# umodular_shiled_amm.net
KiCad netlist of a schematic drawn in EAGLE
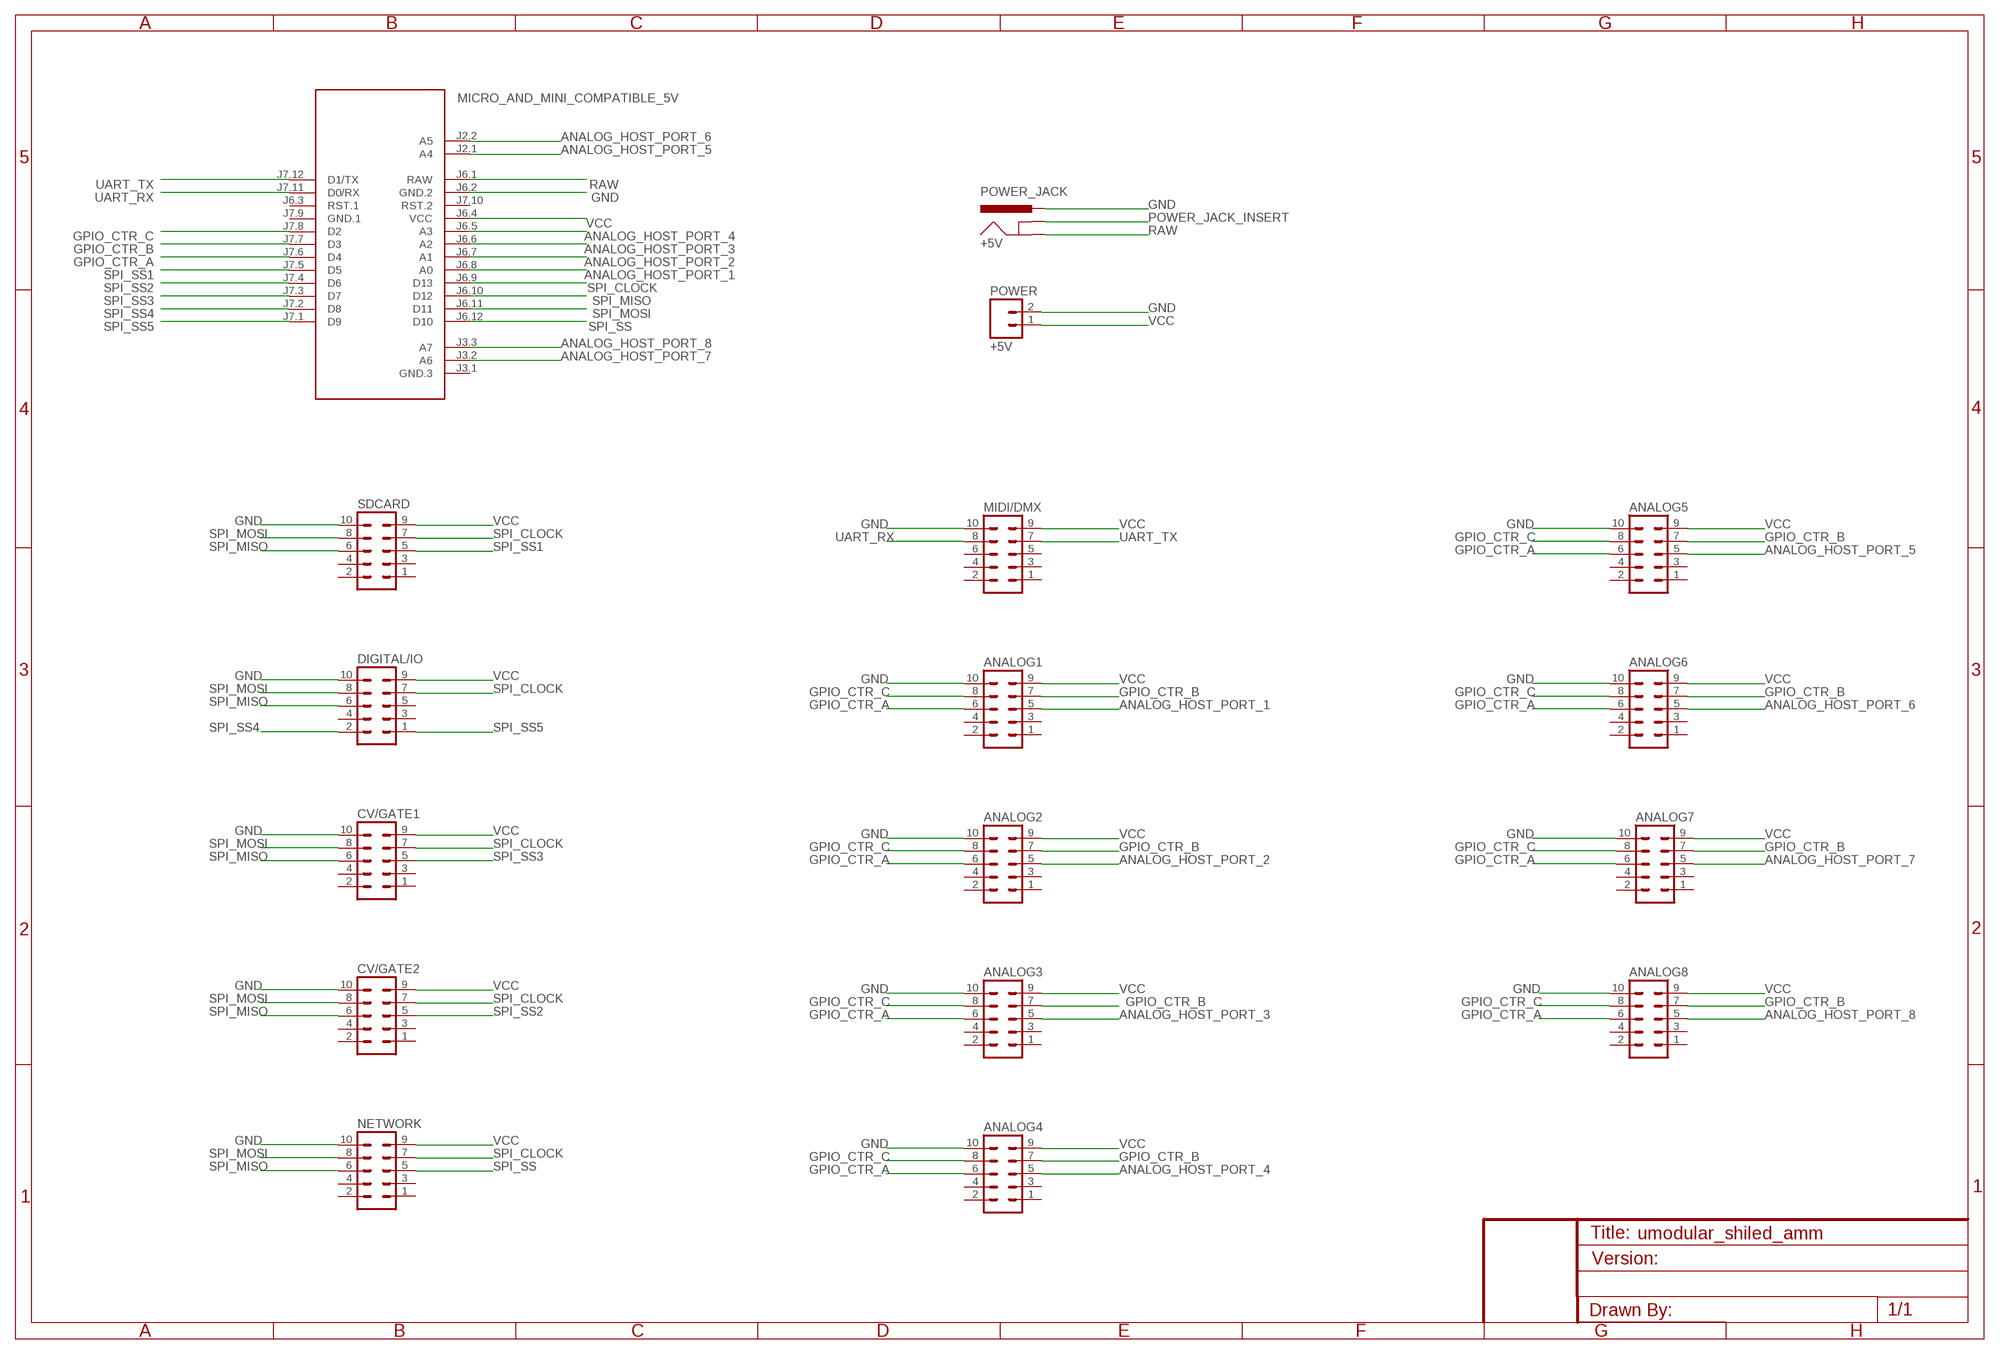
[diagram p0: schematic, sheet 1]

(export (version "E")
  (design (tool "Eeschema 10.0.6"))
  (components
    (comp (ref "+5V")
      (value "POWER_JACK")
      (footprint "eagle-import:POWER_JACK_PTH")
      (libsource (lib "eagle-import") (part "POWER_JACKPTH"))
    )
    (comp (ref "ANALOG1")
      (value "MA05-2")
      (footprint "eagle-import:MA05-2")
      (libsource (lib "eagle-import") (part "MA05-2"))
    )
    (comp (ref "ANALOG2")
      (value "MA05-2")
      (footprint "eagle-import:MA05-2")
      (libsource (lib "eagle-import") (part "MA05-2"))
    )
    (comp (ref "ANALOG3")
      (value "MA05-2")
      (footprint "eagle-import:MA05-2")
      (libsource (lib "eagle-import") (part "MA05-2"))
    )
    (comp (ref "ANALOG4")
      (value "MA05-2")
      (footprint "eagle-import:MA05-2")
      (libsource (lib "eagle-import") (part "MA05-2"))
    )
    (comp (ref "ANALOG5")
      (value "MA05-2")
      (footprint "eagle-import:MA05-2")
      (libsource (lib "eagle-import") (part "MA05-2"))
    )
    (comp (ref "ANALOG6")
      (value "MA05-2")
      (footprint "eagle-import:MA05-2")
      (libsource (lib "eagle-import") (part "MA05-2"))
    )
    (comp (ref "ANALOG7")
      (value "MA05-2")
      (footprint "eagle-import:MA05-2")
      (libsource (lib "eagle-import") (part "MA05-2"))
    )
    (comp (ref "ANALOG8")
      (value "MA05-2")
      (footprint "eagle-import:MA05-2")
      (libsource (lib "eagle-import") (part "MA05-2"))
    )
    (comp (ref "CV/GATE1")
      (value "MA05-2")
      (footprint "eagle-import:MA05-2")
      (libsource (lib "eagle-import") (part "MA05-2"))
    )
    (comp (ref "CV/GATE2")
      (value "MA05-2")
      (footprint "eagle-import:MA05-2")
      (libsource (lib "eagle-import") (part "MA05-2"))
    )
    (comp (ref "DIGITAL/IO")
      (value "MA05-2")
      (footprint "eagle-import:MA05-2")
      (libsource (lib "eagle-import") (part "MA05-2"))
    )
    (comp (ref "MICRO_AND_MINI_COMPATIBLE_5V")
      (value "ARDUINO-PRO-MINI-3.3V#NP")
      (footprint "eagle-import:ARDUINO-PRO-MINI#NP")
      (libsource (lib "eagle-import") (part "ARDUINO-PRO-MINI-#NP3.3V"))
    )
    (comp (ref "MIDI/DMX")
      (value "MA05-2")
      (footprint "eagle-import:MA05-2")
      (libsource (lib "eagle-import") (part "MA05-2"))
    )
    (comp (ref "NETWORK")
      (value "MA05-2")
      (footprint "eagle-import:MA05-2")
      (libsource (lib "eagle-import") (part "MA05-2"))
    )
    (comp (ref "POWER")
      (value "+5V")
      (footprint "eagle-import:1X02_LOCK_LONGPADS")
      (libsource (lib "eagle-import") (part "M02LOCK_LONGPADS"))
    )
    (comp (ref "SDCARD")
      (value "MA05-2")
      (footprint "eagle-import:MA05-2")
      (libsource (lib "eagle-import") (part "MA05-2"))
    )
  )
  (nets
    (net (code "1") (name "/ANALOG_HOST_PORT_1") (class "Default")
      (node (ref "ANALOG1") (pin "5") (pinfunction "5_5") (pintype "passive"))
      (node (ref "MICRO_AND_MINI_COMPATIBLE_5V") (pin "J6.8") (pinfunction "A0_J6.8") (pintype "bidirectional"))
    )
    (net (code "2") (name "/ANALOG_HOST_PORT_2") (class "Default")
      (node (ref "ANALOG2") (pin "5") (pinfunction "5_5") (pintype "passive"))
      (node (ref "MICRO_AND_MINI_COMPATIBLE_5V") (pin "J6.7") (pinfunction "A1_J6.7") (pintype "bidirectional"))
    )
    (net (code "3") (name "/ANALOG_HOST_PORT_3") (class "Default")
      (node (ref "ANALOG3") (pin "5") (pinfunction "5_5") (pintype "passive"))
      (node (ref "MICRO_AND_MINI_COMPATIBLE_5V") (pin "J6.6") (pinfunction "A2_J6.6") (pintype "bidirectional"))
    )
    (net (code "4") (name "/ANALOG_HOST_PORT_4") (class "Default")
      (node (ref "ANALOG4") (pin "5") (pinfunction "5_5") (pintype "passive"))
      (node (ref "MICRO_AND_MINI_COMPATIBLE_5V") (pin "J6.5") (pinfunction "A3_J6.5") (pintype "bidirectional"))
    )
    (net (code "5") (name "/ANALOG_HOST_PORT_5") (class "Default")
      (node (ref "ANALOG5") (pin "5") (pinfunction "5_5") (pintype "passive"))
      (node (ref "MICRO_AND_MINI_COMPATIBLE_5V") (pin "J2.1") (pinfunction "A4_J2.1") (pintype "bidirectional"))
    )
    (net (code "6") (name "/ANALOG_HOST_PORT_6") (class "Default")
      (node (ref "ANALOG6") (pin "5") (pinfunction "5_5") (pintype "passive"))
      (node (ref "MICRO_AND_MINI_COMPATIBLE_5V") (pin "J2.2") (pinfunction "A5_J2.2") (pintype "bidirectional"))
    )
    (net (code "7") (name "/ANALOG_HOST_PORT_7") (class "Default")
      (node (ref "ANALOG7") (pin "5") (pinfunction "5_5") (pintype "passive"))
      (node (ref "MICRO_AND_MINI_COMPATIBLE_5V") (pin "J3.2") (pinfunction "A6_J3.2") (pintype "bidirectional"))
    )
    (net (code "8") (name "/ANALOG_HOST_PORT_8") (class "Default")
      (node (ref "ANALOG8") (pin "5") (pinfunction "5_5") (pintype "passive"))
      (node (ref "MICRO_AND_MINI_COMPATIBLE_5V") (pin "J3.3") (pinfunction "A7_J3.3") (pintype "bidirectional"))
    )
    (net (code "9") (name "/GND") (class "Default")
      (node (ref "+5V") (pin "PWR") (pinfunction "PWR_PWR") (pintype "bidirectional"))
      (node (ref "ANALOG1") (pin "10") (pinfunction "10_10") (pintype "passive"))
      (node (ref "ANALOG2") (pin "10") (pinfunction "10_10") (pintype "passive"))
      (node (ref "ANALOG3") (pin "10") (pinfunction "10_10") (pintype "passive"))
      (node (ref "ANALOG4") (pin "10") (pinfunction "10_10") (pintype "passive"))
      (node (ref "ANALOG5") (pin "10") (pinfunction "10_10") (pintype "passive"))
      (node (ref "ANALOG6") (pin "10") (pinfunction "10_10") (pintype "passive"))
      (node (ref "ANALOG7") (pin "10") (pinfunction "10_10") (pintype "passive"))
      (node (ref "ANALOG8") (pin "10") (pinfunction "10_10") (pintype "passive"))
      (node (ref "CV/GATE1") (pin "10") (pinfunction "10_10") (pintype "passive"))
      (node (ref "CV/GATE2") (pin "10") (pinfunction "10_10") (pintype "passive"))
      (node (ref "DIGITAL/IO") (pin "10") (pinfunction "10_10") (pintype "passive"))
      (node (ref "MICRO_AND_MINI_COMPATIBLE_5V") (pin "J6.2") (pinfunction "GND.2_J6.2") (pintype "power_in"))
      (node (ref "MIDI/DMX") (pin "10") (pinfunction "10_10") (pintype "passive"))
      (node (ref "NETWORK") (pin "10") (pinfunction "10_10") (pintype "passive"))
      (node (ref "POWER") (pin "2") (pinfunction "2_2") (pintype "passive"))
      (node (ref "SDCARD") (pin "10") (pinfunction "10_10") (pintype "passive"))
    )
    (net (code "10") (name "/GND.1") (class "Default")
      (node (ref "MICRO_AND_MINI_COMPATIBLE_5V") (pin "J7.9") (pinfunction "GND.1_J7.9") (pintype "power_in"))
    )
    (net (code "11") (name "/GPIO_CTR_A") (class "Default")
      (node (ref "ANALOG1") (pin "6") (pinfunction "6_6") (pintype "passive"))
      (node (ref "ANALOG2") (pin "6") (pinfunction "6_6") (pintype "passive"))
      (node (ref "ANALOG3") (pin "6") (pinfunction "6_6") (pintype "passive"))
      (node (ref "ANALOG4") (pin "6") (pinfunction "6_6") (pintype "passive"))
      (node (ref "ANALOG5") (pin "6") (pinfunction "6_6") (pintype "passive"))
      (node (ref "ANALOG6") (pin "6") (pinfunction "6_6") (pintype "passive"))
      (node (ref "ANALOG7") (pin "6") (pinfunction "6_6") (pintype "passive"))
      (node (ref "ANALOG8") (pin "6") (pinfunction "6_6") (pintype "passive"))
      (node (ref "MICRO_AND_MINI_COMPATIBLE_5V") (pin "J7.6") (pinfunction "D4_J7.6") (pintype "bidirectional"))
    )
    (net (code "12") (name "/GPIO_CTR_B") (class "Default")
      (node (ref "ANALOG1") (pin "7") (pinfunction "7_7") (pintype "passive"))
      (node (ref "ANALOG2") (pin "7") (pinfunction "7_7") (pintype "passive"))
      (node (ref "ANALOG3") (pin "7") (pinfunction "7_7") (pintype "passive"))
      (node (ref "ANALOG4") (pin "7") (pinfunction "7_7") (pintype "passive"))
      (node (ref "ANALOG5") (pin "7") (pinfunction "7_7") (pintype "passive"))
      (node (ref "ANALOG6") (pin "7") (pinfunction "7_7") (pintype "passive"))
      (node (ref "ANALOG7") (pin "7") (pinfunction "7_7") (pintype "passive"))
      (node (ref "ANALOG8") (pin "7") (pinfunction "7_7") (pintype "passive"))
      (node (ref "MICRO_AND_MINI_COMPATIBLE_5V") (pin "J7.7") (pinfunction "D3_J7.7") (pintype "bidirectional"))
    )
    (net (code "13") (name "/GPIO_CTR_C") (class "Default")
      (node (ref "ANALOG1") (pin "8") (pinfunction "8_8") (pintype "passive"))
      (node (ref "ANALOG2") (pin "8") (pinfunction "8_8") (pintype "passive"))
      (node (ref "ANALOG3") (pin "8") (pinfunction "8_8") (pintype "passive"))
      (node (ref "ANALOG4") (pin "8") (pinfunction "8_8") (pintype "passive"))
      (node (ref "ANALOG5") (pin "8") (pinfunction "8_8") (pintype "passive"))
      (node (ref "ANALOG6") (pin "8") (pinfunction "8_8") (pintype "passive"))
      (node (ref "ANALOG7") (pin "8") (pinfunction "8_8") (pintype "passive"))
      (node (ref "ANALOG8") (pin "8") (pinfunction "8_8") (pintype "passive"))
      (node (ref "MICRO_AND_MINI_COMPATIBLE_5V") (pin "J7.8") (pinfunction "D2_J7.8") (pintype "bidirectional"))
    )
    (net (code "14") (name "/POWER_JACK_INSERT") (class "Default")
      (node (ref "+5V") (pin "GNDBREAK") (pinfunction "GNDBREAK_GNDBREAK") (pintype "bidirectional"))
    )
    (net (code "15") (name "/RAW") (class "Default")
      (node (ref "+5V") (pin "GND") (pinfunction "GND_GND") (pintype "bidirectional"))
      (node (ref "MICRO_AND_MINI_COMPATIBLE_5V") (pin "J6.1") (pinfunction "RAW_J6.1") (pintype "power_in"))
    )
    (net (code "16") (name "/SPI_CLOCK") (class "Default")
      (node (ref "CV/GATE1") (pin "7") (pinfunction "7_7") (pintype "passive"))
      (node (ref "CV/GATE2") (pin "7") (pinfunction "7_7") (pintype "passive"))
      (node (ref "DIGITAL/IO") (pin "7") (pinfunction "7_7") (pintype "passive"))
      (node (ref "MICRO_AND_MINI_COMPATIBLE_5V") (pin "J6.9") (pinfunction "D13_J6.9") (pintype "bidirectional"))
      (node (ref "NETWORK") (pin "7") (pinfunction "7_7") (pintype "passive"))
      (node (ref "SDCARD") (pin "7") (pinfunction "7_7") (pintype "passive"))
    )
    (net (code "17") (name "/SPI_MISO") (class "Default")
      (node (ref "CV/GATE1") (pin "6") (pinfunction "6_6") (pintype "passive"))
      (node (ref "CV/GATE2") (pin "6") (pinfunction "6_6") (pintype "passive"))
      (node (ref "DIGITAL/IO") (pin "6") (pinfunction "6_6") (pintype "passive"))
      (node (ref "MICRO_AND_MINI_COMPATIBLE_5V") (pin "J6.10") (pinfunction "D12_J6.10") (pintype "bidirectional"))
      (node (ref "NETWORK") (pin "6") (pinfunction "6_6") (pintype "passive"))
      (node (ref "SDCARD") (pin "6") (pinfunction "6_6") (pintype "passive"))
    )
    (net (code "18") (name "/SPI_MOSI") (class "Default")
      (node (ref "CV/GATE1") (pin "8") (pinfunction "8_8") (pintype "passive"))
      (node (ref "CV/GATE2") (pin "8") (pinfunction "8_8") (pintype "passive"))
      (node (ref "DIGITAL/IO") (pin "8") (pinfunction "8_8") (pintype "passive"))
      (node (ref "MICRO_AND_MINI_COMPATIBLE_5V") (pin "J6.11") (pinfunction "D11_J6.11") (pintype "bidirectional"))
      (node (ref "NETWORK") (pin "8") (pinfunction "8_8") (pintype "passive"))
      (node (ref "SDCARD") (pin "8") (pinfunction "8_8") (pintype "passive"))
    )
    (net (code "19") (name "/SPI_SS") (class "Default")
      (node (ref "MICRO_AND_MINI_COMPATIBLE_5V") (pin "J6.12") (pinfunction "D10_J6.12") (pintype "bidirectional"))
      (node (ref "NETWORK") (pin "5") (pinfunction "5_5") (pintype "passive"))
    )
    (net (code "20") (name "/SPI_SS1") (class "Default")
      (node (ref "MICRO_AND_MINI_COMPATIBLE_5V") (pin "J7.5") (pinfunction "D5_J7.5") (pintype "bidirectional"))
      (node (ref "SDCARD") (pin "5") (pinfunction "5_5") (pintype "passive"))
    )
    (net (code "21") (name "/SPI_SS2") (class "Default")
      (node (ref "CV/GATE2") (pin "5") (pinfunction "5_5") (pintype "passive"))
      (node (ref "MICRO_AND_MINI_COMPATIBLE_5V") (pin "J7.4") (pinfunction "D6_J7.4") (pintype "bidirectional"))
    )
    (net (code "22") (name "/SPI_SS3") (class "Default")
      (node (ref "CV/GATE1") (pin "5") (pinfunction "5_5") (pintype "passive"))
      (node (ref "MICRO_AND_MINI_COMPATIBLE_5V") (pin "J7.3") (pinfunction "D7_J7.3") (pintype "bidirectional"))
    )
    (net (code "23") (name "/SPI_SS4") (class "Default")
      (node (ref "DIGITAL/IO") (pin "2") (pinfunction "2_2") (pintype "passive"))
      (node (ref "MICRO_AND_MINI_COMPATIBLE_5V") (pin "J7.2") (pinfunction "D8_J7.2") (pintype "bidirectional"))
    )
    (net (code "24") (name "/SPI_SS5") (class "Default")
      (node (ref "DIGITAL/IO") (pin "1") (pinfunction "1_1") (pintype "passive"))
      (node (ref "MICRO_AND_MINI_COMPATIBLE_5V") (pin "J7.1") (pinfunction "D9_J7.1") (pintype "bidirectional"))
    )
    (net (code "25") (name "/UART_RX") (class "Default")
      (node (ref "MICRO_AND_MINI_COMPATIBLE_5V") (pin "J7.11") (pinfunction "D0/RX_J7.11") (pintype "bidirectional"))
      (node (ref "MIDI/DMX") (pin "8") (pinfunction "8_8") (pintype "passive"))
    )
    (net (code "26") (name "/UART_TX") (class "Default")
      (node (ref "MICRO_AND_MINI_COMPATIBLE_5V") (pin "J7.12") (pinfunction "D1/TX_J7.12") (pintype "bidirectional"))
      (node (ref "MIDI/DMX") (pin "7") (pinfunction "7_7") (pintype "passive"))
    )
    (net (code "27") (name "/VCC") (class "Default")
      (node (ref "ANALOG1") (pin "9") (pinfunction "9_9") (pintype "passive"))
      (node (ref "ANALOG2") (pin "9") (pinfunction "9_9") (pintype "passive"))
      (node (ref "ANALOG3") (pin "9") (pinfunction "9_9") (pintype "passive"))
      (node (ref "ANALOG4") (pin "9") (pinfunction "9_9") (pintype "passive"))
      (node (ref "ANALOG5") (pin "9") (pinfunction "9_9") (pintype "passive"))
      (node (ref "ANALOG6") (pin "9") (pinfunction "9_9") (pintype "passive"))
      (node (ref "ANALOG7") (pin "9") (pinfunction "9_9") (pintype "passive"))
      (node (ref "ANALOG8") (pin "9") (pinfunction "9_9") (pintype "passive"))
      (node (ref "CV/GATE1") (pin "9") (pinfunction "9_9") (pintype "passive"))
      (node (ref "CV/GATE2") (pin "9") (pinfunction "9_9") (pintype "passive"))
      (node (ref "DIGITAL/IO") (pin "9") (pinfunction "9_9") (pintype "passive"))
      (node (ref "MICRO_AND_MINI_COMPATIBLE_5V") (pin "J6.4") (pinfunction "VCC_J6.4") (pintype "power_in"))
      (node (ref "MIDI/DMX") (pin "9") (pinfunction "9_9") (pintype "passive"))
      (node (ref "NETWORK") (pin "9") (pinfunction "9_9") (pintype "passive"))
      (node (ref "POWER") (pin "1") (pinfunction "1_1") (pintype "passive"))
      (node (ref "SDCARD") (pin "9") (pinfunction "9_9") (pintype "passive"))
    )
    (net (code "28") (name "unconnected-(ANALOG1-Pad1)") (class "Default")
      (node (ref "ANALOG1") (pin "1") (pinfunction "1_1") (pintype "passive"))
    )
    (net (code "29") (name "unconnected-(ANALOG1-Pad2)") (class "Default")
      (node (ref "ANALOG1") (pin "2") (pinfunction "2_2") (pintype "passive"))
    )
    (net (code "30") (name "unconnected-(ANALOG1-Pad3)") (class "Default")
      (node (ref "ANALOG1") (pin "3") (pinfunction "3_3") (pintype "passive"))
    )
    (net (code "31") (name "unconnected-(ANALOG1-Pad4)") (class "Default")
      (node (ref "ANALOG1") (pin "4") (pinfunction "4_4") (pintype "passive"))
    )
    (net (code "32") (name "unconnected-(ANALOG2-Pad1)") (class "Default")
      (node (ref "ANALOG2") (pin "1") (pinfunction "1_1") (pintype "passive"))
    )
    (net (code "33") (name "unconnected-(ANALOG2-Pad2)") (class "Default")
      (node (ref "ANALOG2") (pin "2") (pinfunction "2_2") (pintype "passive"))
    )
    (net (code "34") (name "unconnected-(ANALOG2-Pad3)") (class "Default")
      (node (ref "ANALOG2") (pin "3") (pinfunction "3_3") (pintype "passive"))
    )
    (net (code "35") (name "unconnected-(ANALOG2-Pad4)") (class "Default")
      (node (ref "ANALOG2") (pin "4") (pinfunction "4_4") (pintype "passive"))
    )
    (net (code "36") (name "unconnected-(ANALOG3-Pad1)") (class "Default")
      (node (ref "ANALOG3") (pin "1") (pinfunction "1_1") (pintype "passive"))
    )
    (net (code "37") (name "unconnected-(ANALOG3-Pad2)") (class "Default")
      (node (ref "ANALOG3") (pin "2") (pinfunction "2_2") (pintype "passive"))
    )
    (net (code "38") (name "unconnected-(ANALOG3-Pad3)") (class "Default")
      (node (ref "ANALOG3") (pin "3") (pinfunction "3_3") (pintype "passive"))
    )
    (net (code "39") (name "unconnected-(ANALOG3-Pad4)") (class "Default")
      (node (ref "ANALOG3") (pin "4") (pinfunction "4_4") (pintype "passive"))
    )
    (net (code "40") (name "unconnected-(ANALOG4-Pad1)") (class "Default")
      (node (ref "ANALOG4") (pin "1") (pinfunction "1_1") (pintype "passive"))
    )
    (net (code "41") (name "unconnected-(ANALOG4-Pad2)") (class "Default")
      (node (ref "ANALOG4") (pin "2") (pinfunction "2_2") (pintype "passive"))
    )
    (net (code "42") (name "unconnected-(ANALOG4-Pad3)") (class "Default")
      (node (ref "ANALOG4") (pin "3") (pinfunction "3_3") (pintype "passive"))
    )
    (net (code "43") (name "unconnected-(ANALOG4-Pad4)") (class "Default")
      (node (ref "ANALOG4") (pin "4") (pinfunction "4_4") (pintype "passive"))
    )
    (net (code "44") (name "unconnected-(ANALOG5-Pad1)") (class "Default")
      (node (ref "ANALOG5") (pin "1") (pinfunction "1_1") (pintype "passive"))
    )
    (net (code "45") (name "unconnected-(ANALOG5-Pad2)") (class "Default")
      (node (ref "ANALOG5") (pin "2") (pinfunction "2_2") (pintype "passive"))
    )
    (net (code "46") (name "unconnected-(ANALOG5-Pad3)") (class "Default")
      (node (ref "ANALOG5") (pin "3") (pinfunction "3_3") (pintype "passive"))
    )
    (net (code "47") (name "unconnected-(ANALOG5-Pad4)") (class "Default")
      (node (ref "ANALOG5") (pin "4") (pinfunction "4_4") (pintype "passive"))
    )
    (net (code "48") (name "unconnected-(ANALOG6-Pad1)") (class "Default")
      (node (ref "ANALOG6") (pin "1") (pinfunction "1_1") (pintype "passive"))
    )
    (net (code "49") (name "unconnected-(ANALOG6-Pad2)") (class "Default")
      (node (ref "ANALOG6") (pin "2") (pinfunction "2_2") (pintype "passive"))
    )
    (net (code "50") (name "unconnected-(ANALOG6-Pad3)") (class "Default")
      (node (ref "ANALOG6") (pin "3") (pinfunction "3_3") (pintype "passive"))
    )
    (net (code "51") (name "unconnected-(ANALOG6-Pad4)") (class "Default")
      (node (ref "ANALOG6") (pin "4") (pinfunction "4_4") (pintype "passive"))
    )
    (net (code "52") (name "unconnected-(ANALOG7-Pad1)") (class "Default")
      (node (ref "ANALOG7") (pin "1") (pinfunction "1_1") (pintype "passive"))
    )
    (net (code "53") (name "unconnected-(ANALOG7-Pad2)") (class "Default")
      (node (ref "ANALOG7") (pin "2") (pinfunction "2_2") (pintype "passive"))
    )
    (net (code "54") (name "unconnected-(ANALOG7-Pad3)") (class "Default")
      (node (ref "ANALOG7") (pin "3") (pinfunction "3_3") (pintype "passive"))
    )
    (net (code "55") (name "unconnected-(ANALOG7-Pad4)") (class "Default")
      (node (ref "ANALOG7") (pin "4") (pinfunction "4_4") (pintype "passive"))
    )
    (net (code "56") (name "unconnected-(ANALOG8-Pad1)") (class "Default")
      (node (ref "ANALOG8") (pin "1") (pinfunction "1_1") (pintype "passive"))
    )
    (net (code "57") (name "unconnected-(ANALOG8-Pad2)") (class "Default")
      (node (ref "ANALOG8") (pin "2") (pinfunction "2_2") (pintype "passive"))
    )
    (net (code "58") (name "unconnected-(ANALOG8-Pad3)") (class "Default")
      (node (ref "ANALOG8") (pin "3") (pinfunction "3_3") (pintype "passive"))
    )
    (net (code "59") (name "unconnected-(ANALOG8-Pad4)") (class "Default")
      (node (ref "ANALOG8") (pin "4") (pinfunction "4_4") (pintype "passive"))
    )
    (net (code "60") (name "unconnected-(CV/GATE1-Pad1)") (class "Default")
      (node (ref "CV/GATE1") (pin "1") (pinfunction "1_1") (pintype "passive"))
    )
    (net (code "61") (name "unconnected-(CV/GATE1-Pad2)") (class "Default")
      (node (ref "CV/GATE1") (pin "2") (pinfunction "2_2") (pintype "passive"))
    )
    (net (code "62") (name "unconnected-(CV/GATE1-Pad3)") (class "Default")
      (node (ref "CV/GATE1") (pin "3") (pinfunction "3_3") (pintype "passive"))
    )
    (net (code "63") (name "unconnected-(CV/GATE1-Pad4)") (class "Default")
      (node (ref "CV/GATE1") (pin "4") (pinfunction "4_4") (pintype "passive"))
    )
    (net (code "64") (name "unconnected-(CV/GATE2-Pad1)") (class "Default")
      (node (ref "CV/GATE2") (pin "1") (pinfunction "1_1") (pintype "passive"))
    )
    (net (code "65") (name "unconnected-(CV/GATE2-Pad2)") (class "Default")
      (node (ref "CV/GATE2") (pin "2") (pinfunction "2_2") (pintype "passive"))
    )
    (net (code "66") (name "unconnected-(CV/GATE2-Pad3)") (class "Default")
      (node (ref "CV/GATE2") (pin "3") (pinfunction "3_3") (pintype "passive"))
    )
    (net (code "67") (name "unconnected-(CV/GATE2-Pad4)") (class "Default")
      (node (ref "CV/GATE2") (pin "4") (pinfunction "4_4") (pintype "passive"))
    )
    (net (code "68") (name "unconnected-(DIGITAL/IO-Pad3)") (class "Default")
      (node (ref "DIGITAL/IO") (pin "3") (pinfunction "3_3") (pintype "passive"))
    )
    (net (code "69") (name "unconnected-(DIGITAL/IO-Pad4)") (class "Default")
      (node (ref "DIGITAL/IO") (pin "4") (pinfunction "4_4") (pintype "passive"))
    )
    (net (code "70") (name "unconnected-(DIGITAL/IO-Pad5)") (class "Default")
      (node (ref "DIGITAL/IO") (pin "5") (pinfunction "5_5") (pintype "passive"))
    )
    (net (code "71") (name "unconnected-(MICRO_AND_MINI_COMPATIBLE_5V-GND.3-PadJ3.1)") (class "Default")
      (node (ref "MICRO_AND_MINI_COMPATIBLE_5V") (pin "J3.1") (pinfunction "GND.3_J3.1") (pintype "bidirectional"))
    )
    (net (code "72") (name "unconnected-(MICRO_AND_MINI_COMPATIBLE_5V-RST.1-PadJ6.3)") (class "Default")
      (node (ref "MICRO_AND_MINI_COMPATIBLE_5V") (pin "J6.3") (pinfunction "RST.1_J6.3") (pintype "bidirectional"))
    )
    (net (code "73") (name "unconnected-(MICRO_AND_MINI_COMPATIBLE_5V-RST.2-PadJ7.10)") (class "Default")
      (node (ref "MICRO_AND_MINI_COMPATIBLE_5V") (pin "J7.10") (pinfunction "RST.2_J7.10") (pintype "bidirectional"))
    )
    (net (code "74") (name "unconnected-(MIDI/DMX-Pad1)") (class "Default")
      (node (ref "MIDI/DMX") (pin "1") (pinfunction "1_1") (pintype "passive"))
    )
    (net (code "75") (name "unconnected-(MIDI/DMX-Pad2)") (class "Default")
      (node (ref "MIDI/DMX") (pin "2") (pinfunction "2_2") (pintype "passive"))
    )
    (net (code "76") (name "unconnected-(MIDI/DMX-Pad3)") (class "Default")
      (node (ref "MIDI/DMX") (pin "3") (pinfunction "3_3") (pintype "passive"))
    )
    (net (code "77") (name "unconnected-(MIDI/DMX-Pad4)") (class "Default")
      (node (ref "MIDI/DMX") (pin "4") (pinfunction "4_4") (pintype "passive"))
    )
    (net (code "78") (name "unconnected-(MIDI/DMX-Pad5)") (class "Default")
      (node (ref "MIDI/DMX") (pin "5") (pinfunction "5_5") (pintype "passive"))
    )
    (net (code "79") (name "unconnected-(MIDI/DMX-Pad6)") (class "Default")
      (node (ref "MIDI/DMX") (pin "6") (pinfunction "6_6") (pintype "passive"))
    )
    (net (code "80") (name "unconnected-(NETWORK-Pad1)") (class "Default")
      (node (ref "NETWORK") (pin "1") (pinfunction "1_1") (pintype "passive"))
    )
    (net (code "81") (name "unconnected-(NETWORK-Pad2)") (class "Default")
      (node (ref "NETWORK") (pin "2") (pinfunction "2_2") (pintype "passive"))
    )
    (net (code "82") (name "unconnected-(NETWORK-Pad3)") (class "Default")
      (node (ref "NETWORK") (pin "3") (pinfunction "3_3") (pintype "passive"))
    )
    (net (code "83") (name "unconnected-(NETWORK-Pad4)") (class "Default")
      (node (ref "NETWORK") (pin "4") (pinfunction "4_4") (pintype "passive"))
    )
    (net (code "84") (name "unconnected-(SDCARD-Pad1)") (class "Default")
      (node (ref "SDCARD") (pin "1") (pinfunction "1_1") (pintype "passive"))
    )
    (net (code "85") (name "unconnected-(SDCARD-Pad2)") (class "Default")
      (node (ref "SDCARD") (pin "2") (pinfunction "2_2") (pintype "passive"))
    )
    (net (code "86") (name "unconnected-(SDCARD-Pad3)") (class "Default")
      (node (ref "SDCARD") (pin "3") (pinfunction "3_3") (pintype "passive"))
    )
    (net (code "87") (name "unconnected-(SDCARD-Pad4)") (class "Default")
      (node (ref "SDCARD") (pin "4") (pinfunction "4_4") (pintype "passive"))
    )
  )
)
